# PDM-S10-V00-SDCard.net
KiCad netlist of a schematic drawn in Altium Designer
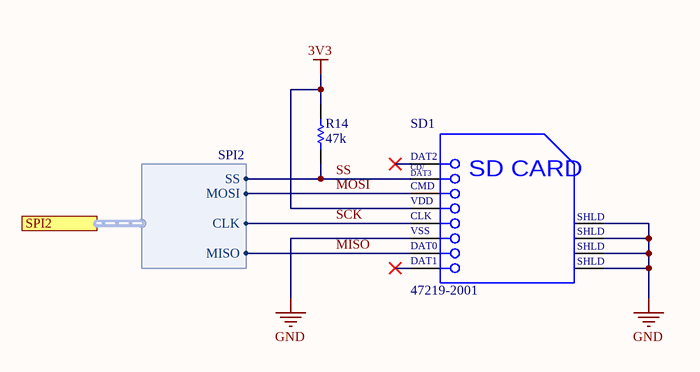
[diagram p0: PDM-S10-V00-SDCard.SchDoc]

(export (version "E")
  (design (tool "Eeschema 10.0.6"))
  (components
    (comp (ref "R14")
      (value "47k")
      (footprint "Res_ThinFilm_0603")
      (description "Resistor, SMD, 47k, 0.1W, 5%, 0603")
      (libsource (lib "StandardResistors") (part "47k 5% 0603"))
    )
    (comp (ref "SD1")
      (value "47219-2001")
      (footprint "MOLX-47219-2001-8_V")
      (description "MicroSD Card Connector, Hinge Type, -40 to 85 degC, 8-Pin SMD, RoHS, Tape and Reel")
      (fields (field (name "MANUFACTURER") "Molex"))
      (libsource (lib "QUTMS_SDCardLibrary") (part "47219-2001"))
    )
  )
  (nets
    (net (code "2") (name "/MISO") (class "Default")
      (node (ref "SD1") (pin "7") (pinfunction "DAT0_7") (pintype "passive"))
    )
    (net (code "3") (name "/MOSI") (class "Default")
      (node (ref "SD1") (pin "3") (pinfunction "CMD_3") (pintype "passive"))
    )
    (net (code "4") (name "/SCK") (class "Default")
      (node (ref "SD1") (pin "5") (pinfunction "CLK_5") (pintype "passive"))
    )
    (net (code "5") (name "/SS") (class "Default")
      (node (ref "R14") (pin "1") (pinfunction "1_1") (pintype "passive"))
      (node (ref "SD1") (pin "2") (pinfunction "CD/DAT3_2") (pintype "passive"))
    )
    (net (code "7") (name "3V3") (class "Default")
      (node (ref "R14") (pin "2") (pinfunction "2_2") (pintype "passive"))
      (node (ref "SD1") (pin "4") (pinfunction "VDD_4") (pintype "passive"))
    )
    (net (code "8") (name "GND") (class "Default")
      (node (ref "SD1") (pin "10") (pinfunction "SHLD_10") (pintype "passive"))
      (node (ref "SD1") (pin "11") (pinfunction "SHLD_11") (pintype "passive"))
      (node (ref "SD1") (pin "12") (pinfunction "SHLD_12") (pintype "passive"))
      (node (ref "SD1") (pin "6") (pinfunction "VSS_6") (pintype "passive"))
      (node (ref "SD1") (pin "9") (pinfunction "SHLD_9") (pintype "passive"))
    )
    (net (code "9") (name "unconnected-(SD1-DAT1-Pad8)") (class "Default")
      (node (ref "SD1") (pin "8") (pinfunction "DAT1_8") (pintype "passive+no_connect"))
    )
    (net (code "10") (name "unconnected-(SD1-DAT2-Pad1)") (class "Default")
      (node (ref "SD1") (pin "1") (pinfunction "DAT2_1") (pintype "passive+no_connect"))
    )
  )
)
